# warps_v30.net
KiCad netlist of a schematic drawn in EAGLE
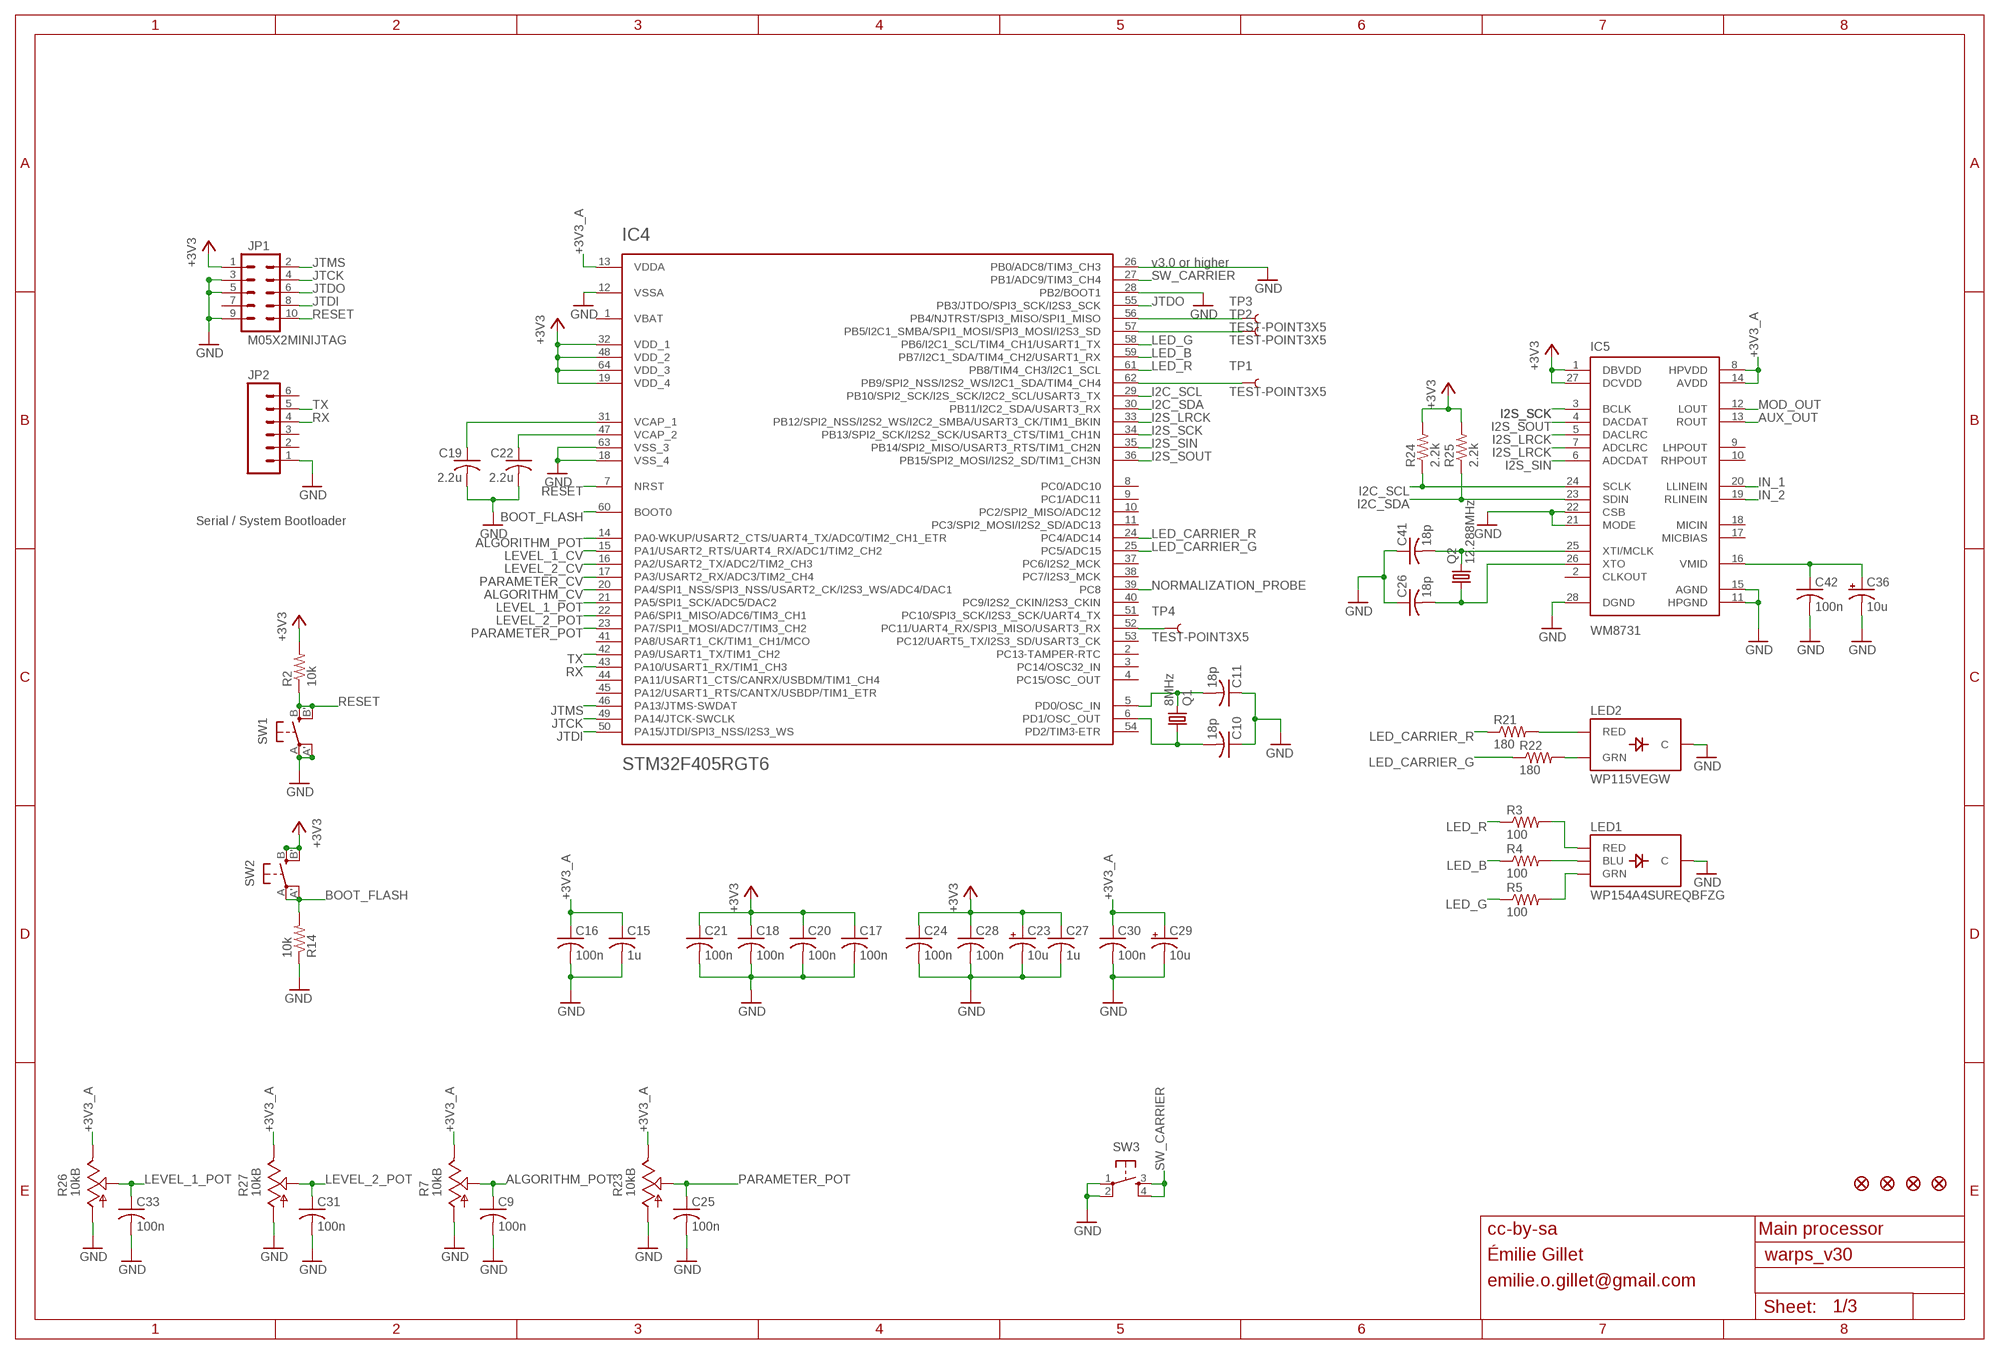
[diagram p0: schematic, sheet 1]
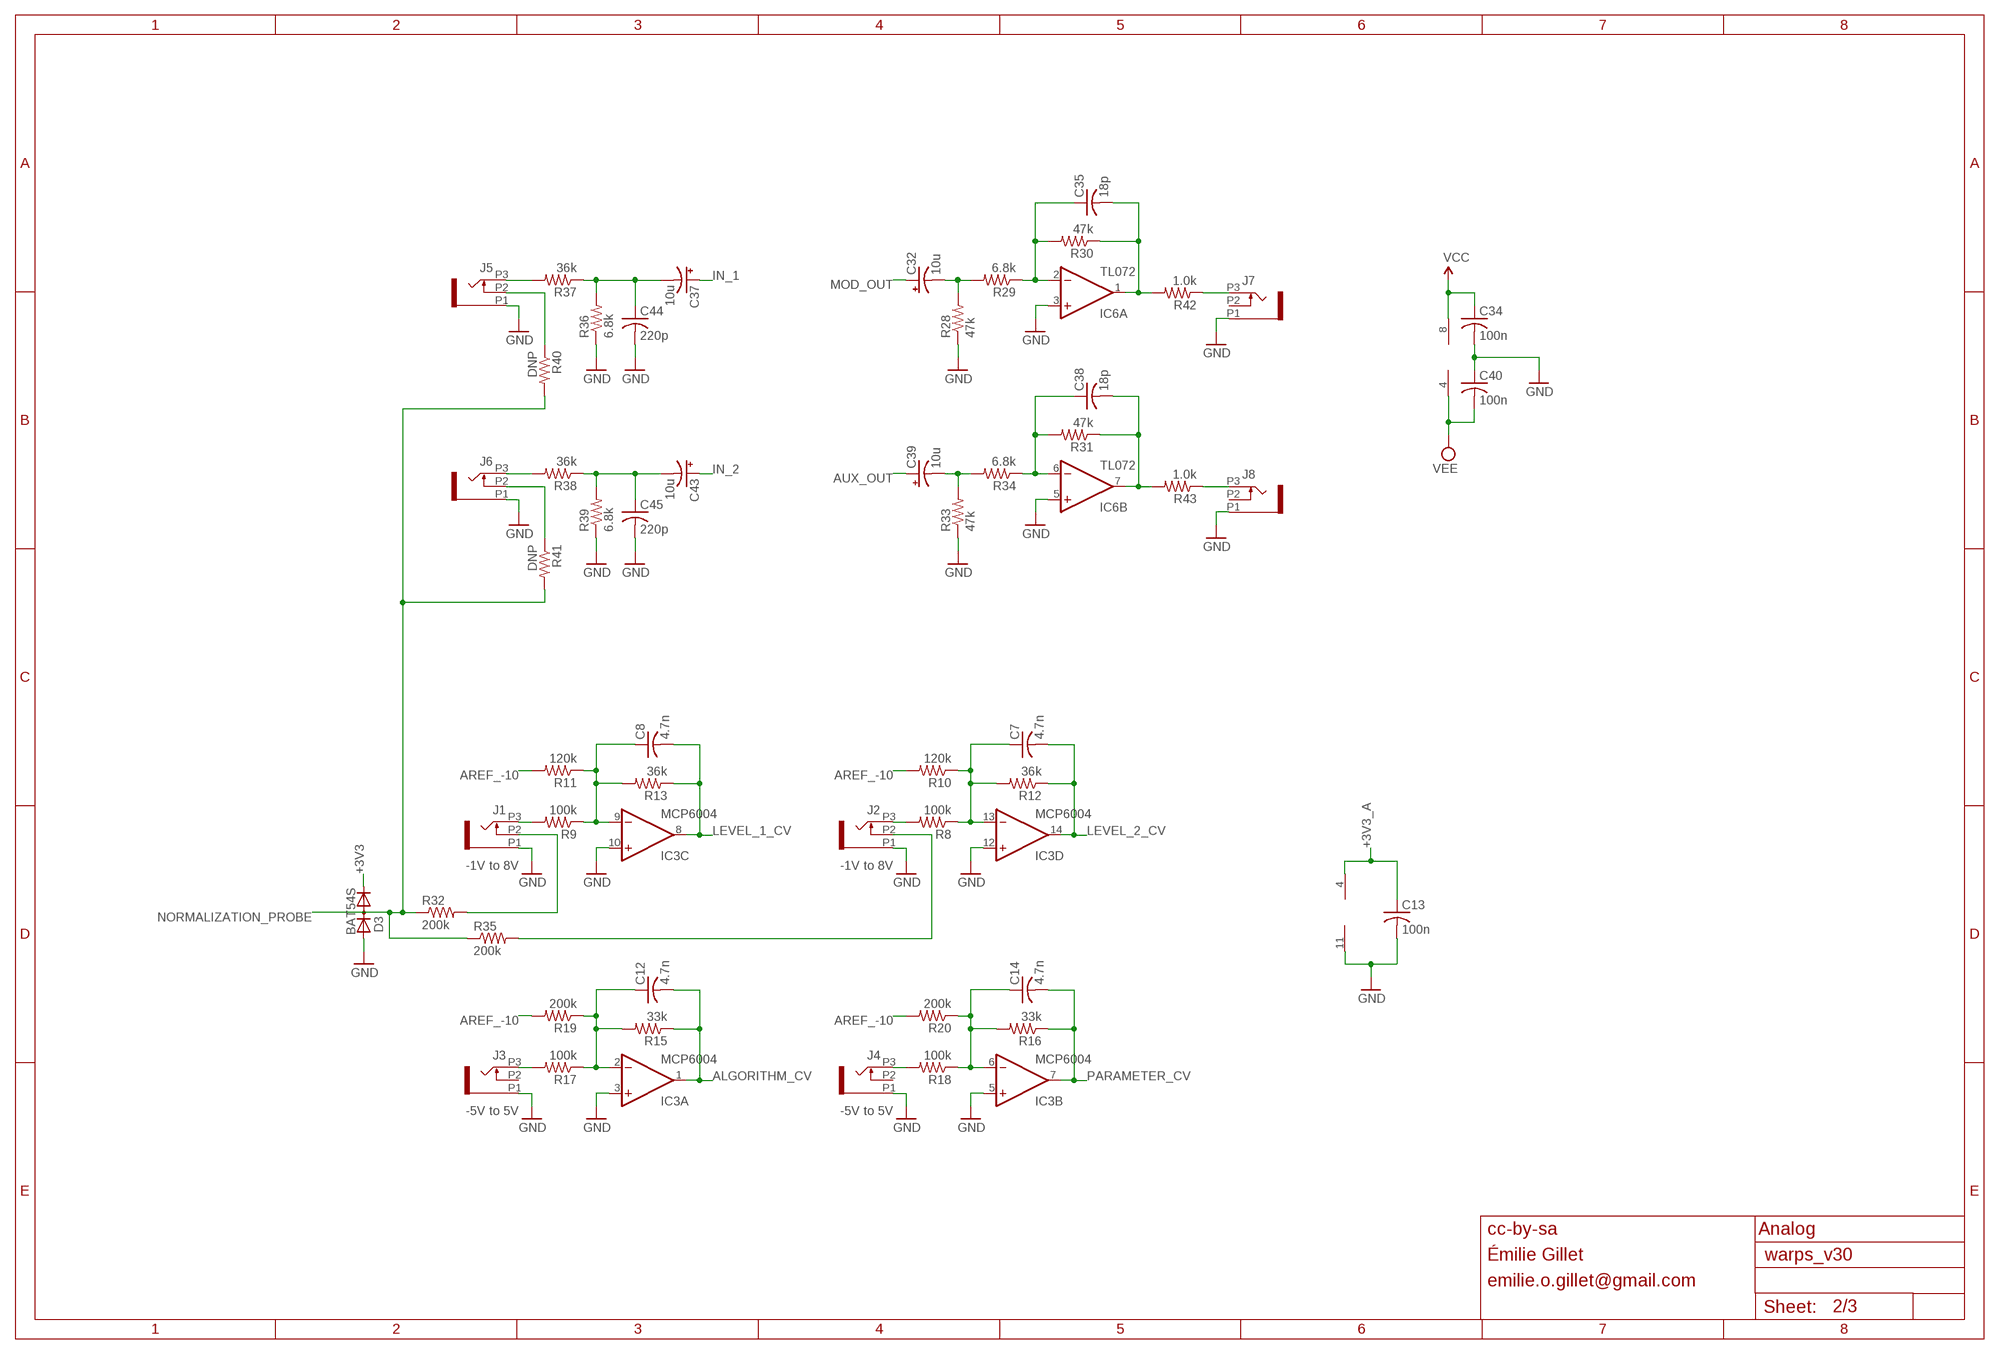
[diagram p1: schematic, sheet 2]
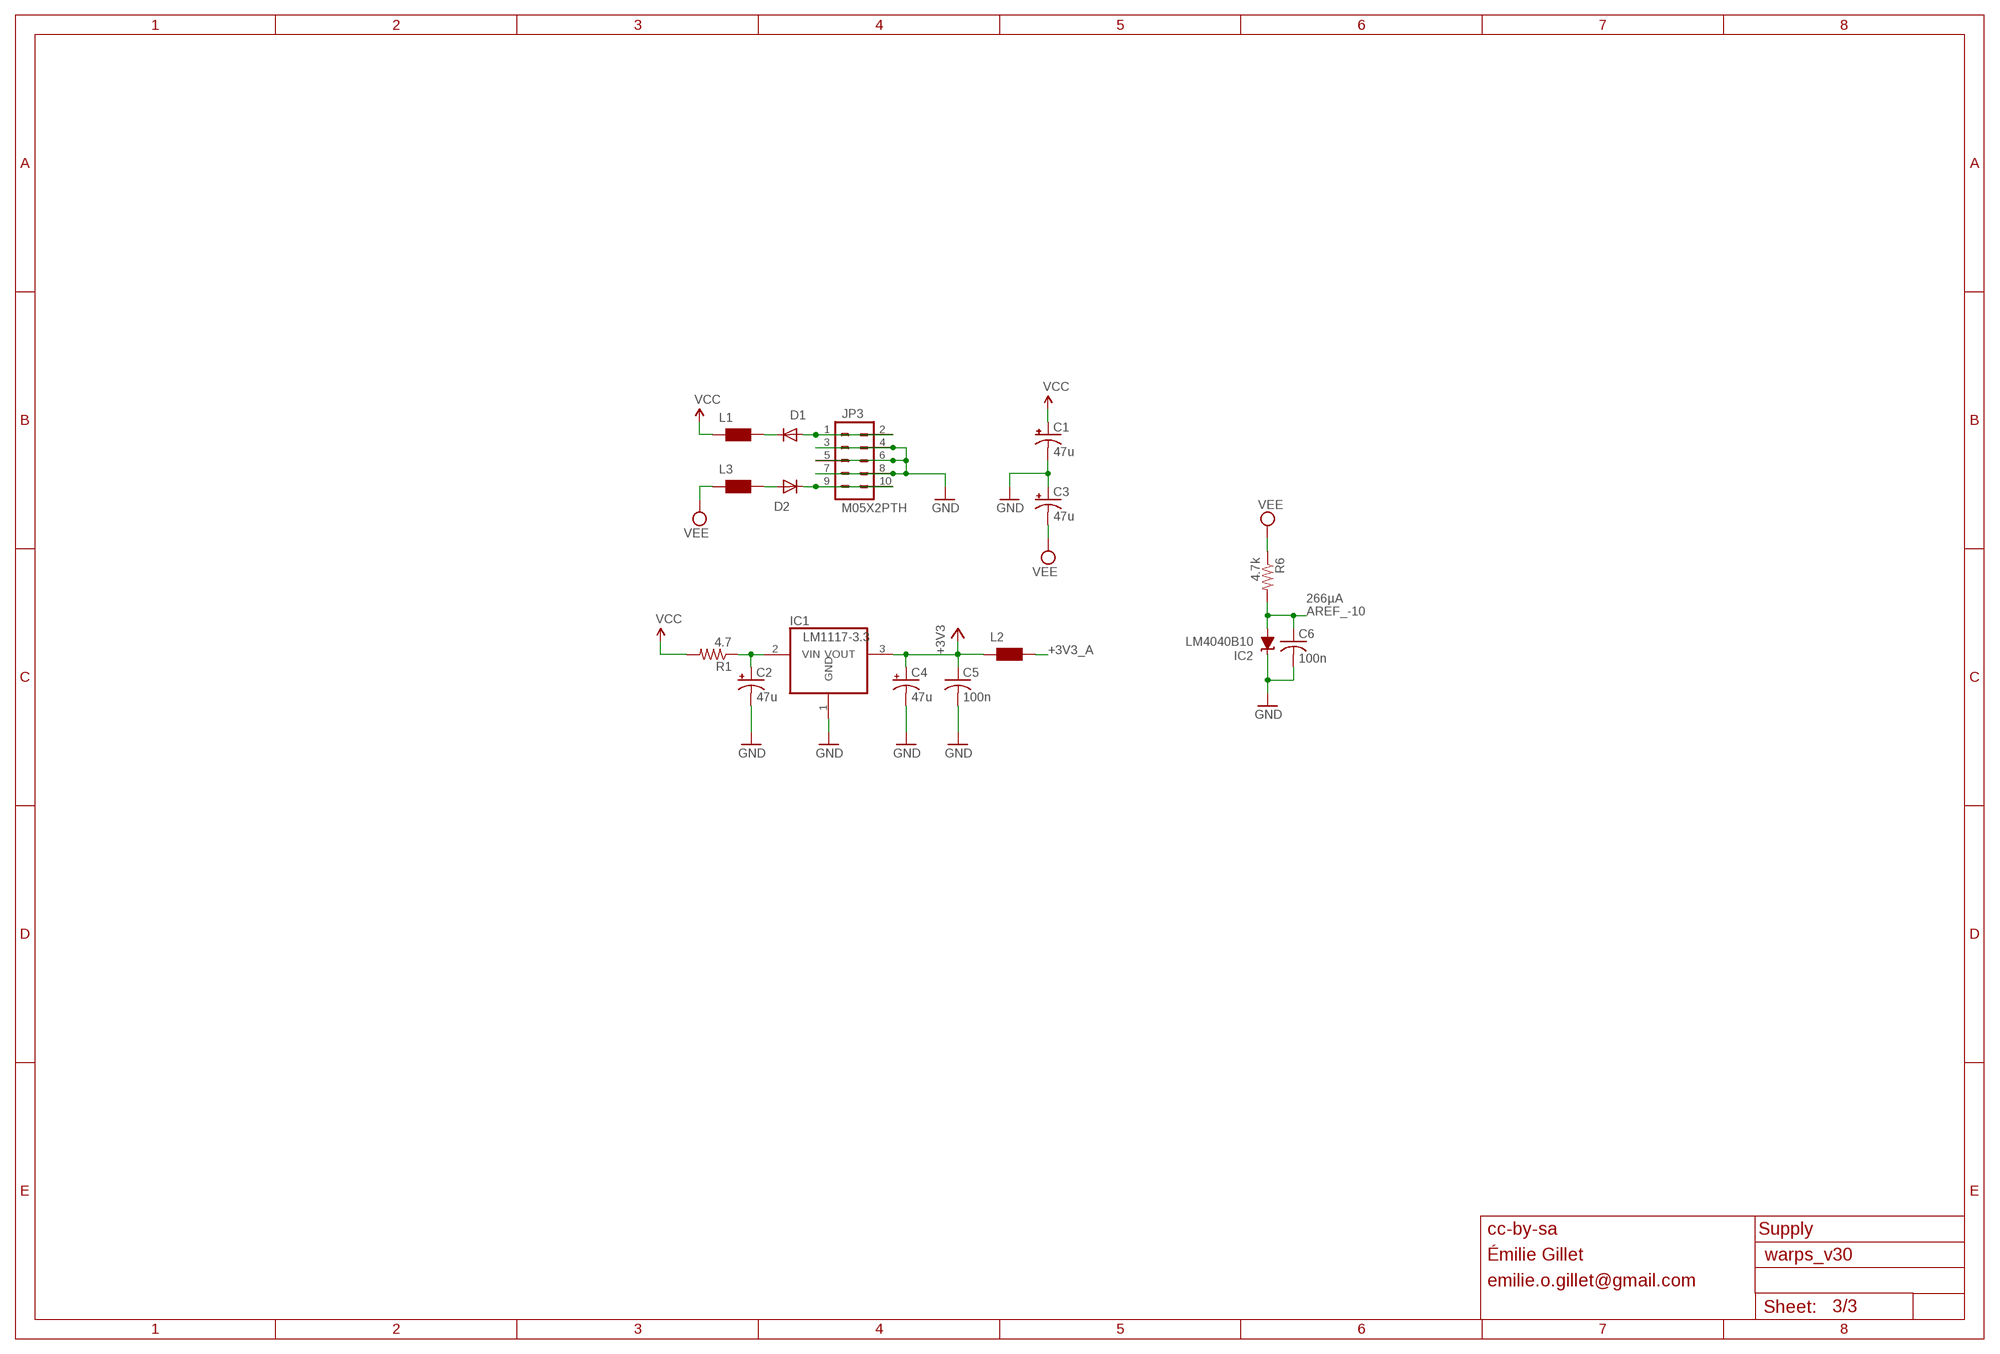
[diagram p2: schematic, sheet 3]

(export (version "E")
  (design (tool "Eeschema 10.0.6"))
  (components
    (comp (ref "C1")
      (value "47u")
      (footprint "eagle-import:PANASONIC_D")
      (libsource (lib "eagle-import") (part "CPOL-USD"))
    )
    (comp (ref "C2")
      (value "47u")
      (footprint "eagle-import:PANASONIC_D")
      (libsource (lib "eagle-import") (part "CPOL-USD"))
    )
    (comp (ref "C3")
      (value "47u")
      (footprint "eagle-import:PANASONIC_D")
      (libsource (lib "eagle-import") (part "CPOL-USD"))
    )
    (comp (ref "C4")
      (value "47u")
      (footprint "eagle-import:PANASONIC_D")
      (libsource (lib "eagle-import") (part "CPOL-USD"))
    )
    (comp (ref "C5")
      (value "100n")
      (footprint "eagle-import:C0603")
      (libsource (lib "eagle-import") (part "C-USC0603"))
    )
    (comp (ref "C6")
      (value "100n")
      (footprint "eagle-import:C0603")
      (libsource (lib "eagle-import") (part "C-USC0603"))
    )
    (comp (ref "D1")
      (value "1N5819HW")
      (footprint "eagle-import:SOD123")
      (libsource (lib "eagle-import") (part "DIODE-SOD123"))
    )
    (comp (ref "D2")
      (value "1N5819HW")
      (footprint "eagle-import:SOD123")
      (libsource (lib "eagle-import") (part "DIODE-SOD123"))
    )
    (comp (ref "IC1")
      (value "LM1117-3.3")
      (footprint "eagle-import:TO252")
      (libsource (lib "eagle-import") (part "REG1117T"))
    )
    (comp (ref "IC2")
      (value "LM4040B10")
      (footprint "eagle-import:DBZ_R-PDSO-G3")
      (libsource (lib "eagle-import") (part "LM4041DBZB12"))
    )
    (comp (ref "JP3")
      (value "M05X2PTH")
      (footprint "eagle-import:AVR_ICSP")
      (libsource (lib "eagle-import") (part "M05X2PTH"))
    )
    (comp (ref "L1")
      (value "WE-CBF_0603")
      (footprint "eagle-import:0603")
      (libsource (lib "eagle-import") (part "WE-CBF_0603"))
    )
    (comp (ref "L2")
      (value "WE-CBF_0603")
      (footprint "eagle-import:0603")
      (libsource (lib "eagle-import") (part "WE-CBF_0603"))
    )
    (comp (ref "L3")
      (value "WE-CBF_0603")
      (footprint "eagle-import:0603")
      (libsource (lib "eagle-import") (part "WE-CBF_0603"))
    )
    (comp (ref "R1")
      (value "4.7")
      (footprint "eagle-import:R1206")
      (libsource (lib "eagle-import") (part "R-US_R1206"))
    )
    (comp (ref "R6")
      (value "4.7k")
      (footprint "eagle-import:R0603")
      (libsource (lib "eagle-import") (part "R-US_R0603"))
    )
    (comp (ref "C7")
      (value "4.7n")
      (footprint "eagle-import:C0603")
      (libsource (lib "eagle-import") (part "C-USC0603"))
    )
    (comp (ref "C8")
      (value "4.7n")
      (footprint "eagle-import:C0603")
      (libsource (lib "eagle-import") (part "C-USC0603"))
    )
    (comp (ref "C12")
      (value "4.7n")
      (footprint "eagle-import:C0603")
      (libsource (lib "eagle-import") (part "C-USC0603"))
    )
    (comp (ref "C13")
      (value "100n")
      (footprint "eagle-import:C0603")
      (libsource (lib "eagle-import") (part "C-USC0603"))
    )
    (comp (ref "C14")
      (value "4.7n")
      (footprint "eagle-import:C0603")
      (libsource (lib "eagle-import") (part "C-USC0603"))
    )
    (comp (ref "C32")
      (value "10u")
      (footprint "eagle-import:PANASONIC_A")
      (libsource (lib "eagle-import") (part "CPOL-USA"))
    )
    (comp (ref "C34")
      (value "100n")
      (footprint "eagle-import:C0603")
      (libsource (lib "eagle-import") (part "C-USC0603"))
    )
    (comp (ref "C35")
      (value "18p")
      (footprint "eagle-import:C0603")
      (libsource (lib "eagle-import") (part "C-USC0603"))
    )
    (comp (ref "C37")
      (value "10u")
      (footprint "eagle-import:PANASONIC_A")
      (libsource (lib "eagle-import") (part "CPOL-USA"))
    )
    (comp (ref "C38")
      (value "18p")
      (footprint "eagle-import:C0603")
      (libsource (lib "eagle-import") (part "C-USC0603"))
    )
    (comp (ref "C39")
      (value "10u")
      (footprint "eagle-import:PANASONIC_A")
      (libsource (lib "eagle-import") (part "CPOL-USA"))
    )
    (comp (ref "C40")
      (value "100n")
      (footprint "eagle-import:C0603")
      (libsource (lib "eagle-import") (part "C-USC0603"))
    )
    (comp (ref "C43")
      (value "10u")
      (footprint "eagle-import:PANASONIC_A")
      (libsource (lib "eagle-import") (part "CPOL-USA"))
    )
    (comp (ref "C44")
      (value "220p")
      (footprint "eagle-import:C0603")
      (libsource (lib "eagle-import") (part "C-USC0603"))
    )
    (comp (ref "C45")
      (value "220p")
      (footprint "eagle-import:C0603")
      (libsource (lib "eagle-import") (part "C-USC0603"))
    )
    (comp (ref "D3")
      (value "BAT54S")
      (footprint "eagle-import:SOT23")
      (libsource (lib "eagle-import") (part "DIODE_2CACA-SOT23"))
    )
    (comp (ref "IC3")
      (value "MCP6004")
      (footprint "eagle-import:SO14")
      (libsource (lib "eagle-import") (part "TL074D"))
    )
    (comp (ref "IC6")
      (value "TL072")
      (footprint "eagle-import:SO08")
      (libsource (lib "eagle-import") (part "TL072D"))
    )
    (comp (ref "J1")
      (value "PJ301_THONKICONN6")
      (footprint "eagle-import:WQP_PJ_301M6")
      (libsource (lib "eagle-import") (part "PJ301_THONKICONN6"))
    )
    (comp (ref "J2")
      (value "PJ301_THONKICONN6")
      (footprint "eagle-import:WQP_PJ_301M6")
      (libsource (lib "eagle-import") (part "PJ301_THONKICONN6"))
    )
    (comp (ref "J3")
      (value "PJ301_THONKICONN6")
      (footprint "eagle-import:WQP_PJ_301M6")
      (libsource (lib "eagle-import") (part "PJ301_THONKICONN6"))
    )
    (comp (ref "J4")
      (value "PJ301_THONKICONN6")
      (footprint "eagle-import:WQP_PJ_301M6")
      (libsource (lib "eagle-import") (part "PJ301_THONKICONN6"))
    )
    (comp (ref "J5")
      (value "PJ301_THONKICONN6")
      (footprint "eagle-import:WQP_PJ_301M6")
      (libsource (lib "eagle-import") (part "PJ301_THONKICONN6"))
    )
    (comp (ref "J6")
      (value "PJ301_THONKICONN6")
      (footprint "eagle-import:WQP_PJ_301M6")
      (libsource (lib "eagle-import") (part "PJ301_THONKICONN6"))
    )
    (comp (ref "J7")
      (value "PJ301_THONKICONN6")
      (footprint "eagle-import:WQP_PJ_301M6")
      (libsource (lib "eagle-import") (part "PJ301_THONKICONN6"))
    )
    (comp (ref "J8")
      (value "PJ301_THONKICONN6")
      (footprint "eagle-import:WQP_PJ_301M6")
      (libsource (lib "eagle-import") (part "PJ301_THONKICONN6"))
    )
    (comp (ref "R8")
      (value "100k")
      (footprint "eagle-import:R0603")
      (libsource (lib "eagle-import") (part "R-US_R0603"))
    )
    (comp (ref "R9")
      (value "100k")
      (footprint "eagle-import:R0603")
      (libsource (lib "eagle-import") (part "R-US_R0603"))
    )
    (comp (ref "R10")
      (value "120k")
      (footprint "eagle-import:R0603")
      (libsource (lib "eagle-import") (part "R-US_R0603"))
    )
    (comp (ref "R11")
      (value "120k")
      (footprint "eagle-import:R0603")
      (libsource (lib "eagle-import") (part "R-US_R0603"))
    )
    (comp (ref "R12")
      (value "36k")
      (footprint "eagle-import:R0603")
      (libsource (lib "eagle-import") (part "R-US_R0603"))
    )
    (comp (ref "R13")
      (value "36k")
      (footprint "eagle-import:R0603")
      (libsource (lib "eagle-import") (part "R-US_R0603"))
    )
    (comp (ref "R15")
      (value "33k")
      (footprint "eagle-import:R0603")
      (libsource (lib "eagle-import") (part "R-US_R0603"))
    )
    (comp (ref "R16")
      (value "33k")
      (footprint "eagle-import:R0603")
      (libsource (lib "eagle-import") (part "R-US_R0603"))
    )
    (comp (ref "R17")
      (value "100k")
      (footprint "eagle-import:R0603")
      (libsource (lib "eagle-import") (part "R-US_R0603"))
    )
    (comp (ref "R18")
      (value "100k")
      (footprint "eagle-import:R0603")
      (libsource (lib "eagle-import") (part "R-US_R0603"))
    )
    (comp (ref "R19")
      (value "200k")
      (footprint "eagle-import:R0603")
      (libsource (lib "eagle-import") (part "R-US_R0603"))
    )
    (comp (ref "R20")
      (value "200k")
      (footprint "eagle-import:R0603")
      (libsource (lib "eagle-import") (part "R-US_R0603"))
    )
    (comp (ref "R28")
      (value "47k")
      (footprint "eagle-import:R0603")
      (libsource (lib "eagle-import") (part "R-US_R0603"))
    )
    (comp (ref "R29")
      (value "6.8k")
      (footprint "eagle-import:R0603")
      (libsource (lib "eagle-import") (part "R-US_R0603"))
    )
    (comp (ref "R30")
      (value "47k")
      (footprint "eagle-import:R0603")
      (libsource (lib "eagle-import") (part "R-US_R0603"))
    )
    (comp (ref "R31")
      (value "47k")
      (footprint "eagle-import:R0603")
      (libsource (lib "eagle-import") (part "R-US_R0603"))
    )
    (comp (ref "R32")
      (value "200k")
      (footprint "eagle-import:R0603")
      (libsource (lib "eagle-import") (part "R-US_R0603"))
    )
    (comp (ref "R33")
      (value "47k")
      (footprint "eagle-import:R0603")
      (libsource (lib "eagle-import") (part "R-US_R0603"))
    )
    (comp (ref "R34")
      (value "6.8k")
      (footprint "eagle-import:R0603")
      (libsource (lib "eagle-import") (part "R-US_R0603"))
    )
    (comp (ref "R35")
      (value "200k")
      (footprint "eagle-import:R0603")
      (libsource (lib "eagle-import") (part "R-US_R0603"))
    )
    (comp (ref "R36")
      (value "6.8k")
      (footprint "eagle-import:R0603")
      (libsource (lib "eagle-import") (part "R-US_R0603"))
    )
    (comp (ref "R37")
      (value "36k")
      (footprint "eagle-import:R0603")
      (libsource (lib "eagle-import") (part "R-US_R0603"))
    )
    (comp (ref "R38")
      (value "36k")
      (footprint "eagle-import:R0603")
      (libsource (lib "eagle-import") (part "R-US_R0603"))
    )
    (comp (ref "R39")
      (value "6.8k")
      (footprint "eagle-import:R0603")
      (libsource (lib "eagle-import") (part "R-US_R0603"))
    )
    (comp (ref "R40")
      (value "DNP")
      (footprint "eagle-import:R0603")
      (libsource (lib "eagle-import") (part "R-US_R0603"))
    )
    (comp (ref "R41")
      (value "DNP")
      (footprint "eagle-import:R0603")
      (libsource (lib "eagle-import") (part "R-US_R0603"))
    )
    (comp (ref "R42")
      (value "1.0k")
      (footprint "eagle-import:R0603")
      (libsource (lib "eagle-import") (part "R-US_R0603"))
    )
    (comp (ref "R43")
      (value "1.0k")
      (footprint "eagle-import:R0603")
      (libsource (lib "eagle-import") (part "R-US_R0603"))
    )
    (comp (ref "C9")
      (value "100n")
      (footprint "eagle-import:C0603")
      (libsource (lib "eagle-import") (part "C-USC0603"))
    )
    (comp (ref "C10")
      (value "18p")
      (footprint "eagle-import:C0603")
      (libsource (lib "eagle-import") (part "C-USC0603"))
    )
    (comp (ref "C11")
      (value "18p")
      (footprint "eagle-import:C0603")
      (libsource (lib "eagle-import") (part "C-USC0603"))
    )
    (comp (ref "C15")
      (value "1u")
      (footprint "eagle-import:C0603")
      (libsource (lib "eagle-import") (part "C-USC0603"))
    )
    (comp (ref "C16")
      (value "100n")
      (footprint "eagle-import:C0603")
      (libsource (lib "eagle-import") (part "C-USC0603"))
    )
    (comp (ref "C17")
      (value "100n")
      (footprint "eagle-import:C0603")
      (libsource (lib "eagle-import") (part "C-USC0603"))
    )
    (comp (ref "C18")
      (value "100n")
      (footprint "eagle-import:C0603")
      (libsource (lib "eagle-import") (part "C-USC0603"))
    )
    (comp (ref "C19")
      (value "2.2u")
      (footprint "eagle-import:C0805")
      (libsource (lib "eagle-import") (part "C-USC0805"))
    )
    (comp (ref "C20")
      (value "100n")
      (footprint "eagle-import:C0603")
      (libsource (lib "eagle-import") (part "C-USC0603"))
    )
    (comp (ref "C21")
      (value "100n")
      (footprint "eagle-import:C0603")
      (libsource (lib "eagle-import") (part "C-USC0603"))
    )
    (comp (ref "C22")
      (value "2.2u")
      (footprint "eagle-import:C0805")
      (libsource (lib "eagle-import") (part "C-USC0805"))
    )
    (comp (ref "C23")
      (value "10u")
      (footprint "eagle-import:PANASONIC_A")
      (libsource (lib "eagle-import") (part "CPOL-USA"))
    )
    (comp (ref "C24")
      (value "100n")
      (footprint "eagle-import:C0603")
      (libsource (lib "eagle-import") (part "C-USC0603"))
    )
    (comp (ref "C25")
      (value "100n")
      (footprint "eagle-import:C0603")
      (libsource (lib "eagle-import") (part "C-USC0603"))
    )
    (comp (ref "C26")
      (value "18p")
      (footprint "eagle-import:C0603")
      (libsource (lib "eagle-import") (part "C-USC0603"))
    )
    (comp (ref "C27")
      (value "1u")
      (footprint "eagle-import:C0603")
      (libsource (lib "eagle-import") (part "C-USC0603"))
    )
    (comp (ref "C28")
      (value "100n")
      (footprint "eagle-import:C0603")
      (libsource (lib "eagle-import") (part "C-USC0603"))
    )
    (comp (ref "C29")
      (value "10u")
      (footprint "eagle-import:PANASONIC_A")
      (libsource (lib "eagle-import") (part "CPOL-USA"))
    )
    (comp (ref "C30")
      (value "100n")
      (footprint "eagle-import:C0603")
      (libsource (lib "eagle-import") (part "C-USC0603"))
    )
    (comp (ref "C31")
      (value "100n")
      (footprint "eagle-import:C0603")
      (libsource (lib "eagle-import") (part "C-USC0603"))
    )
    (comp (ref "C33")
      (value "100n")
      (footprint "eagle-import:C0603")
      (libsource (lib "eagle-import") (part "C-USC0603"))
    )
    (comp (ref "C36")
      (value "10u")
      (footprint "eagle-import:PANASONIC_A")
      (libsource (lib "eagle-import") (part "CPOL-USA"))
    )
    (comp (ref "C41")
      (value "18p")
      (footprint "eagle-import:C0603")
      (libsource (lib "eagle-import") (part "C-USC0603"))
    )
    (comp (ref "C42")
      (value "100n")
      (footprint "eagle-import:C0603")
      (libsource (lib "eagle-import") (part "C-USC0603"))
    )
    (comp (ref "F1")
      (value "FIDUCIAL1X2")
      (footprint "eagle-import:FIDUCIAL-1X2")
      (libsource (lib "eagle-import") (part "FIDUCIAL1X2"))
    )
    (comp (ref "F2")
      (value "FIDUCIAL1X2")
      (footprint "eagle-import:FIDUCIAL-1X2")
      (libsource (lib "eagle-import") (part "FIDUCIAL1X2"))
    )
    (comp (ref "F3")
      (value "FIDUCIAL1X2")
      (footprint "eagle-import:FIDUCIAL-1X2")
      (libsource (lib "eagle-import") (part "FIDUCIAL1X2"))
    )
    (comp (ref "F4")
      (value "FIDUCIAL1X2")
      (footprint "eagle-import:FIDUCIAL-1X2")
      (libsource (lib "eagle-import") (part "FIDUCIAL1X2"))
    )
    (comp (ref "IC4")
      (value "STM32F405RGT6")
      (footprint "eagle-import:TQFP-10X10-64")
      (libsource (lib "eagle-import") (part "STM32F20X"))
    )
    (comp (ref "IC5")
      (value "WM8731")
      (footprint "eagle-import:SSOP28")
      (libsource (lib "eagle-import") (part "WM8731"))
    )
    (comp (ref "JP1")
      (value "M05X2MINIJTAG")
      (footprint "eagle-import:2X5-1.27")
      (libsource (lib "eagle-import") (part "M05X2MINIJTAG"))
    )
    (comp (ref "JP2")
      (value "M06SIP")
      (footprint "eagle-import:1X06")
      (libsource (lib "eagle-import") (part "M06SIP"))
    )
    (comp (ref "LED1")
      (value "WP154A4SUREQBFZG")
      (footprint "eagle-import:LED-TRICOLOR-THROUGHHOLE")
      (libsource (lib "eagle-import") (part "LED-TRICOLOR-THROUGHHOLE"))
    )
    (comp (ref "LED2")
      (value "WP115VEGW")
      (footprint "eagle-import:LED-BICOLOR-THROUGHHOLE")
      (libsource (lib "eagle-import") (part "LED-BICOLOR-THROUGHHOLE"))
    )
    (comp (ref "Q1")
      (value "8MHz")
      (footprint "eagle-import:HC49UP")
      (libsource (lib "eagle-import") (part "CRYSTALHC49UP"))
    )
    (comp (ref "Q2")
      (value "12.288MHz")
      (footprint "eagle-import:HC49UP")
      (libsource (lib "eagle-import") (part "CRYSTALHC49UP"))
    )
    (comp (ref "R2")
      (value "10k")
      (footprint "eagle-import:R0603")
      (libsource (lib "eagle-import") (part "R-US_R0603"))
    )
    (comp (ref "R3")
      (value "100")
      (footprint "eagle-import:R0603")
      (libsource (lib "eagle-import") (part "R-US_R0603"))
    )
    (comp (ref "R4")
      (value "100")
      (footprint "eagle-import:R0603")
      (libsource (lib "eagle-import") (part "R-US_R0603"))
    )
    (comp (ref "R5")
      (value "100")
      (footprint "eagle-import:R0603")
      (libsource (lib "eagle-import") (part "R-US_R0603"))
    )
    (comp (ref "R7")
      (value "10kB")
      (footprint "eagle-import:ALPS_POT_VERTICAL_PS")
      (libsource (lib "eagle-import") (part "POT_USVERTICAL_PS"))
    )
    (comp (ref "R14")
      (value "10k")
      (footprint "eagle-import:R0603")
      (libsource (lib "eagle-import") (part "R-US_R0603"))
    )
    (comp (ref "R21")
      (value "180")
      (footprint "eagle-import:R0603")
      (libsource (lib "eagle-import") (part "R-US_R0603"))
    )
    (comp (ref "R22")
      (value "180")
      (footprint "eagle-import:R0603")
      (libsource (lib "eagle-import") (part "R-US_R0603"))
    )
    (comp (ref "R23")
      (value "10kB")
      (footprint "eagle-import:ALPS_POT_VERTICAL_PS")
      (libsource (lib "eagle-import") (part "POT_USVERTICAL_PS"))
    )
    (comp (ref "R24")
      (value "2.2k")
      (footprint "eagle-import:R0603")
      (libsource (lib "eagle-import") (part "R-US_R0603"))
    )
    (comp (ref "R25")
      (value "2.2k")
      (footprint "eagle-import:R0603")
      (libsource (lib "eagle-import") (part "R-US_R0603"))
    )
    (comp (ref "R26")
      (value "10kB")
      (footprint "eagle-import:ALPS_POT_VERTICAL")
      (libsource (lib "eagle-import") (part "POT_USVERTICAL"))
    )
    (comp (ref "R27")
      (value "10kB")
      (footprint "eagle-import:ALPS_POT_VERTICAL")
      (libsource (lib "eagle-import") (part "POT_USVERTICAL"))
    )
    (comp (ref "SW1")
      (value "EVQQ2")
      (footprint "eagle-import:EVQ-Q2")
      (libsource (lib "eagle-import") (part "EVQQ2"))
    )
    (comp (ref "SW2")
      (value "EVQQ2")
      (footprint "eagle-import:EVQ-Q2")
      (libsource (lib "eagle-import") (part "EVQQ2"))
    )
    (comp (ref "SW3")
      (value "TAC_SWITCHPTH")
      (footprint "eagle-import:TACTILE-PTH")
      (libsource (lib "eagle-import") (part "TAC_SWITCHPTH"))
    )
    (comp (ref "TP1")
      (value "TEST-POINT3X5")
      (footprint "eagle-import:PAD.03X.05")
      (libsource (lib "eagle-import") (part "TEST-POINT3X5"))
    )
    (comp (ref "TP2")
      (value "TEST-POINT3X5")
      (footprint "eagle-import:PAD.03X.05")
      (libsource (lib "eagle-import") (part "TEST-POINT3X5"))
    )
    (comp (ref "TP3")
      (value "TEST-POINT3X5")
      (footprint "eagle-import:PAD.03X.05")
      (libsource (lib "eagle-import") (part "TEST-POINT3X5"))
    )
    (comp (ref "TP4")
      (value "TEST-POINT3X5")
      (footprint "eagle-import:PAD.03X.05")
      (libsource (lib "eagle-import") (part "TEST-POINT3X5"))
    )
  )
  (nets
    (net (code "1") (name "+3V3") (class "Default")
      (node (ref "C17") (pin "1") (pinfunction "1_1") (pintype "passive"))
      (node (ref "C18") (pin "1") (pinfunction "1_1") (pintype "passive"))
      (node (ref "C20") (pin "1") (pinfunction "1_1") (pintype "passive"))
      (node (ref "C21") (pin "1") (pinfunction "1_1") (pintype "passive"))
      (node (ref "C23") (pin "+") (pinfunction "+_+") (pintype "passive"))
      (node (ref "C24") (pin "1") (pinfunction "1_1") (pintype "passive"))
      (node (ref "C27") (pin "1") (pinfunction "1_1") (pintype "passive"))
      (node (ref "C28") (pin "1") (pinfunction "1_1") (pintype "passive"))
      (node (ref "C4") (pin "+") (pinfunction "+_+") (pintype "passive"))
      (node (ref "C5") (pin "1") (pinfunction "1_1") (pintype "passive"))
      (node (ref "D3") (pin "2") (pinfunction "C_2") (pintype "passive"))
      (node (ref "IC1") (pin "3") (pinfunction "VOUT_3") (pintype "output"))
      (node (ref "IC4") (pin "19") (pinfunction "VDD_4_19") (pintype "power_in"))
      (node (ref "IC4") (pin "32") (pinfunction "VDD_1_32") (pintype "power_in"))
      (node (ref "IC4") (pin "48") (pinfunction "VDD_2_48") (pintype "power_in"))
      (node (ref "IC4") (pin "64") (pinfunction "VDD_3_64") (pintype "power_in"))
      (node (ref "IC5") (pin "1") (pinfunction "DBVDD_1") (pintype "bidirectional"))
      (node (ref "IC5") (pin "27") (pinfunction "DCVDD_27") (pintype "bidirectional"))
      (node (ref "JP1") (pin "1") (pinfunction "1_1") (pintype "passive"))
      (node (ref "L2") (pin "1") (pinfunction "1_1") (pintype "passive"))
      (node (ref "R2") (pin "2") (pinfunction "2_2") (pintype "passive"))
      (node (ref "R24") (pin "2") (pinfunction "2_2") (pintype "passive"))
      (node (ref "R25") (pin "2") (pinfunction "2_2") (pintype "passive"))
      (node (ref "SW2") (pin "B") (pinfunction "S_B") (pintype "passive"))
      (node (ref "SW2") (pin "B'") (pinfunction "S1_B'") (pintype "passive"))
    )
    (net (code "2") (name "+3V3_A") (class "Default")
      (node (ref "C13") (pin "1") (pinfunction "1_1") (pintype "passive"))
      (node (ref "C15") (pin "1") (pinfunction "1_1") (pintype "passive"))
      (node (ref "C16") (pin "1") (pinfunction "1_1") (pintype "passive"))
      (node (ref "C29") (pin "+") (pinfunction "+_+") (pintype "passive"))
      (node (ref "C30") (pin "1") (pinfunction "1_1") (pintype "passive"))
      (node (ref "IC3") (pin "4") (pinfunction "V+_4") (pintype "power_in"))
      (node (ref "IC4") (pin "13") (pinfunction "VDDA_13") (pintype "power_in"))
      (node (ref "IC5") (pin "14") (pinfunction "AVDD_14") (pintype "bidirectional"))
      (node (ref "IC5") (pin "8") (pinfunction "HPVDD_8") (pintype "bidirectional"))
      (node (ref "L2") (pin "2") (pinfunction "2_2") (pintype "passive"))
      (node (ref "R23") (pin "P$1") (pinfunction "E_P$1") (pintype "passive"))
      (node (ref "R26") (pin "P$1") (pinfunction "E_P$1") (pintype "passive"))
      (node (ref "R27") (pin "P$1") (pinfunction "E_P$1") (pintype "passive"))
      (node (ref "R7") (pin "P$1") (pinfunction "E_P$1") (pintype "passive"))
    )
    (net (code "3") (name "ALGORITHM_CV") (class "Default")
      (node (ref "C12") (pin "2") (pinfunction "2_2") (pintype "passive"))
      (node (ref "IC3") (pin "1") (pinfunction "OUT_1") (pintype "output"))
      (node (ref "IC4") (pin "20") (pinfunction "PA4/SPI1_NSS/SPI3_NSS/USART2_CK/I2S3_WS/ADC4/DAC1_20") (pintype "bidirectional"))
      (node (ref "R15") (pin "1") (pinfunction "1_1") (pintype "passive"))
    )
    (net (code "4") (name "ALGORITHM_POT") (class "Default")
      (node (ref "C9") (pin "1") (pinfunction "1_1") (pintype "passive"))
      (node (ref "IC4") (pin "14") (pinfunction "PA0-WKUP/USART2_CTS/UART4_TX/ADC0/TIM2_CH1_ETR_14") (pintype "bidirectional"))
      (node (ref "R7") (pin "P$2") (pinfunction "S_P$2") (pintype "passive"))
    )
    (net (code "5") (name "AREF_-10") (class "Default")
      (node (ref "C6") (pin "1") (pinfunction "1_1") (pintype "passive"))
      (node (ref "IC2") (pin "2") (pinfunction "A_2") (pintype "passive"))
      (node (ref "R10") (pin "2") (pinfunction "2_2") (pintype "passive"))
      (node (ref "R11") (pin "2") (pinfunction "2_2") (pintype "passive"))
      (node (ref "R19") (pin "2") (pinfunction "2_2") (pintype "passive"))
      (node (ref "R20") (pin "2") (pinfunction "2_2") (pintype "passive"))
      (node (ref "R6") (pin "2") (pinfunction "2_2") (pintype "passive"))
    )
    (net (code "6") (name "AUX_OUT") (class "Default")
      (node (ref "C39") (pin "+") (pinfunction "+_+") (pintype "passive"))
      (node (ref "IC5") (pin "13") (pinfunction "ROUT_13") (pintype "bidirectional"))
    )
    (net (code "7") (name "BOOT_FLASH") (class "Default")
      (node (ref "IC4") (pin "60") (pinfunction "BOOT0_60") (pintype "bidirectional"))
      (node (ref "R14") (pin "2") (pinfunction "2_2") (pintype "passive"))
      (node (ref "SW2") (pin "A") (pinfunction "P_A") (pintype "passive"))
      (node (ref "SW2") (pin "A'") (pinfunction "P1_A'") (pintype "passive"))
    )
    (net (code "8") (name "GND") (class "Default")
      (node (ref "C1") (pin "-") (pinfunction "-_-") (pintype "passive"))
      (node (ref "C10") (pin "1") (pinfunction "1_1") (pintype "passive"))
      (node (ref "C11") (pin "1") (pinfunction "1_1") (pintype "passive"))
      (node (ref "C13") (pin "2") (pinfunction "2_2") (pintype "passive"))
      (node (ref "C15") (pin "2") (pinfunction "2_2") (pintype "passive"))
      (node (ref "C16") (pin "2") (pinfunction "2_2") (pintype "passive"))
      (node (ref "C17") (pin "2") (pinfunction "2_2") (pintype "passive"))
      (node (ref "C18") (pin "2") (pinfunction "2_2") (pintype "passive"))
      (node (ref "C19") (pin "2") (pinfunction "2_2") (pintype "passive"))
      (node (ref "C2") (pin "-") (pinfunction "-_-") (pintype "passive"))
      (node (ref "C20") (pin "2") (pinfunction "2_2") (pintype "passive"))
      (node (ref "C21") (pin "2") (pinfunction "2_2") (pintype "passive"))
      (node (ref "C22") (pin "2") (pinfunction "2_2") (pintype "passive"))
      (node (ref "C23") (pin "-") (pinfunction "-_-") (pintype "passive"))
      (node (ref "C24") (pin "2") (pinfunction "2_2") (pintype "passive"))
      (node (ref "C25") (pin "2") (pinfunction "2_2") (pintype "passive"))
      (node (ref "C26") (pin "1") (pinfunction "1_1") (pintype "passive"))
      (node (ref "C27") (pin "2") (pinfunction "2_2") (pintype "passive"))
      (node (ref "C28") (pin "2") (pinfunction "2_2") (pintype "passive"))
      (node (ref "C29") (pin "-") (pinfunction "-_-") (pintype "passive"))
      (node (ref "C3") (pin "+") (pinfunction "+_+") (pintype "passive"))
      (node (ref "C30") (pin "2") (pinfunction "2_2") (pintype "passive"))
      (node (ref "C31") (pin "2") (pinfunction "2_2") (pintype "passive"))
      (node (ref "C33") (pin "2") (pinfunction "2_2") (pintype "passive"))
      (node (ref "C34") (pin "2") (pinfunction "2_2") (pintype "passive"))
      (node (ref "C36") (pin "-") (pinfunction "-_-") (pintype "passive"))
      (node (ref "C4") (pin "-") (pinfunction "-_-") (pintype "passive"))
      (node (ref "C40") (pin "1") (pinfunction "1_1") (pintype "passive"))
      (node (ref "C41") (pin "1") (pinfunction "1_1") (pintype "passive"))
      (node (ref "C42") (pin "2") (pinfunction "2_2") (pintype "passive"))
      (node (ref "C44") (pin "2") (pinfunction "2_2") (pintype "passive"))
      (node (ref "C45") (pin "2") (pinfunction "2_2") (pintype "passive"))
      (node (ref "C5") (pin "2") (pinfunction "2_2") (pintype "passive"))
      (node (ref "C6") (pin "2") (pinfunction "2_2") (pintype "passive"))
      (node (ref "C9") (pin "2") (pinfunction "2_2") (pintype "passive"))
      (node (ref "D3") (pin "1") (pinfunction "A_1") (pintype "passive"))
      (node (ref "IC1") (pin "1") (pinfunction "GND_1") (pintype "power_in"))
      (node (ref "IC2") (pin "1") (pinfunction "C_1") (pintype "passive"))
      (node (ref "IC3") (pin "10") (pinfunction "+IN_10") (pintype "input"))
      (node (ref "IC3") (pin "11") (pinfunction "V-_11") (pintype "power_in"))
      (node (ref "IC3") (pin "12") (pinfunction "+IN_12") (pintype "input"))
      (node (ref "IC3") (pin "3") (pinfunction "+IN_3") (pintype "input"))
      (node (ref "IC3") (pin "5") (pinfunction "+IN_5") (pintype "input"))
      (node (ref "IC4") (pin "12") (pinfunction "VSSA_12") (pintype "power_in"))
      (node (ref "IC4") (pin "18") (pinfunction "VSS_4_18") (pintype "power_in"))
      (node (ref "IC4") (pin "26") (pinfunction "PB0/ADC8/TIM3_CH3_26") (pintype "bidirectional"))
      (node (ref "IC4") (pin "28") (pinfunction "PB2/BOOT1_28") (pintype "bidirectional"))
      (node (ref "IC4") (pin "63") (pinfunction "VSS_3_63") (pintype "power_in"))
      (node (ref "IC5") (pin "11") (pinfunction "HPGND_11") (pintype "bidirectional"))
      (node (ref "IC5") (pin "15") (pinfunction "AGND_15") (pintype "bidirectional"))
      (node (ref "IC5") (pin "21") (pinfunction "MODE_21") (pintype "bidirectional"))
      (node (ref "IC5") (pin "22") (pinfunction "CSB_22") (pintype "bidirectional"))
      (node (ref "IC5") (pin "28") (pinfunction "DGND_28") (pintype "bidirectional"))
      (node (ref "IC6") (pin "3") (pinfunction "+IN_3") (pintype "input"))
      (node (ref "IC6") (pin "5") (pinfunction "+IN_5") (pintype "input"))
      (node (ref "J1") (pin "P1") (pinfunction "1_P1") (pintype "passive"))
      (node (ref "J2") (pin "P1") (pinfunction "1_P1") (pintype "passive"))
      (node (ref "J3") (pin "P1") (pinfunction "1_P1") (pintype "passive"))
      (node (ref "J4") (pin "P1") (pinfunction "1_P1") (pintype "passive"))
      (node (ref "J5") (pin "P1") (pinfunction "1_P1") (pintype "passive"))
      (node (ref "J6") (pin "P1") (pinfunction "1_P1") (pintype "passive"))
      (node (ref "J7") (pin "P1") (pinfunction "1_P1") (pintype "passive"))
      (node (ref "J8") (pin "P1") (pinfunction "1_P1") (pintype "passive"))
      (node (ref "JP1") (pin "3") (pinfunction "3_3") (pintype "passive"))
      (node (ref "JP1") (pin "5") (pinfunction "5_5") (pintype "passive"))
      (node (ref "JP1") (pin "9") (pinfunction "9_9") (pintype "passive"))
      (node (ref "JP2") (pin "1") (pinfunction "1_1") (pintype "passive"))
      (node (ref "JP3") (pin "3") (pinfunction "3_3") (pintype "passive"))
      (node (ref "JP3") (pin "4") (pinfunction "4_4") (pintype "passive"))
      (node (ref "JP3") (pin "5") (pinfunction "5_5") (pintype "passive"))
      (node (ref "JP3") (pin "6") (pinfunction "6_6") (pintype "passive"))
      (node (ref "JP3") (pin "7") (pinfunction "7_7") (pintype "passive"))
      (node (ref "JP3") (pin "8") (pinfunction "8_8") (pintype "passive"))
      (node (ref "LED1") (pin "GND") (pinfunction "C_GND") (pintype "bidirectional"))
      (node (ref "LED2") (pin "2") (pinfunction "C_2") (pintype "bidirectional"))
      (node (ref "R14") (pin "1") (pinfunction "1_1") (pintype "passive"))
      (node (ref "R23") (pin "P$3") (pinfunction "A_P$3") (pintype "passive"))
      (node (ref "R26") (pin "P$3") (pinfunction "A_P$3") (pintype "passive"))
      (node (ref "R27") (pin "P$3") (pinfunction "A_P$3") (pintype "passive"))
      (node (ref "R28") (pin "1") (pinfunction "1_1") (pintype "passive"))
      (node (ref "R33") (pin "1") (pinfunction "1_1") (pintype "passive"))
      (node (ref "R36") (pin "1") (pinfunction "1_1") (pintype "passive"))
      (node (ref "R39") (pin "1") (pinfunction "1_1") (pintype "passive"))
      (node (ref "R7") (pin "P$3") (pinfunction "A_P$3") (pintype "passive"))
      (node (ref "SW1") (pin "A") (pinfunction "P_A") (pintype "passive"))
      (node (ref "SW1") (pin "A'") (pinfunction "P1_A'") (pintype "passive"))
      (node (ref "SW3") (pin "1") (pinfunction "1_1") (pintype "passive"))
      (node (ref "SW3") (pin "2") (pinfunction "2_2") (pintype "passive"))
    )
    (net (code "9") (name "I2C_SCL") (class "Default")
      (node (ref "IC4") (pin "29") (pinfunction "PB10/SPI2_SCK/I2S_SCK/I2C2_SCL/USART3_TX_29") (pintype "bidirectional"))
      (node (ref "IC5") (pin "24") (pinfunction "SCLK_24") (pintype "bidirectional"))
      (node (ref "R24") (pin "1") (pinfunction "1_1") (pintype "passive"))
    )
    (net (code "10") (name "I2C_SDA") (class "Default")
      (node (ref "IC4") (pin "30") (pinfunction "PB11/I2C2_SDA/USART3_RX_30") (pintype "bidirectional"))
      (node (ref "IC5") (pin "23") (pinfunction "SDIN_23") (pintype "bidirectional"))
      (node (ref "R25") (pin "1") (pinfunction "1_1") (pintype "passive"))
    )
    (net (code "11") (name "I2S_LRCK") (class "Default")
      (node (ref "IC4") (pin "33") (pinfunction "PB12/SPI2_NSS/I2S2_WS/I2C2_SMBA/USART3_CK/TIM1_BKIN_33") (pintype "bidirectional"))
      (node (ref "IC5") (pin "5") (pinfunction "DACLRC_5") (pintype "bidirectional"))
      (node (ref "IC5") (pin "7") (pinfunction "ADCLRC_7") (pintype "bidirectional"))
    )
    (net (code "12") (name "I2S_SCK") (class "Default")
      (node (ref "IC4") (pin "34") (pinfunction "PB13/SPI2_SCK/I2S2_SCK/USART3_CTS/TIM1_CH1N_34") (pintype "bidirectional"))
      (node (ref "IC5") (pin "3") (pinfunction "BCLK_3") (pintype "bidirectional"))
    )
    (net (code "13") (name "I2S_SIN") (class "Default")
      (node (ref "IC4") (pin "35") (pinfunction "PB14/SPI2_MISO/USART3_RTS/TIM1_CH2N_35") (pintype "bidirectional"))
      (node (ref "IC5") (pin "6") (pinfunction "ADCDAT_6") (pintype "bidirectional"))
    )
    (net (code "14") (name "I2S_SOUT") (class "Default")
      (node (ref "IC4") (pin "36") (pinfunction "PB15/SPI2_MOSI/I2S2_SD/TIM1_CH3N_36") (pintype "bidirectional"))
      (node (ref "IC5") (pin "4") (pinfunction "DACDAT_4") (pintype "bidirectional"))
    )
    (net (code "15") (name "IN_1") (class "Default")
      (node (ref "C37") (pin "+") (pinfunction "+_+") (pintype "passive"))
      (node (ref "IC5") (pin "20") (pinfunction "LLINEIN_20") (pintype "bidirectional"))
    )
    (net (code "16") (name "IN_2") (class "Default")
      (node (ref "C43") (pin "+") (pinfunction "+_+") (pintype "passive"))
      (node (ref "IC5") (pin "19") (pinfunction "RLINEIN_19") (pintype "bidirectional"))
    )
    (net (code "17") (name "JTCK") (class "Default")
      (node (ref "IC4") (pin "49") (pinfunction "PA14/JTCK-SWCLK_49") (pintype "bidirectional"))
      (node (ref "JP1") (pin "4") (pinfunction "4_4") (pintype "passive"))
    )
    (net (code "18") (name "JTDI") (class "Default")
      (node (ref "IC4") (pin "50") (pinfunction "PA15/JTDI/SPI3_NSS/I2S3_WS_50") (pintype "bidirectional"))
      (node (ref "JP1") (pin "8") (pinfunction "8_8") (pintype "passive"))
    )
    (net (code "19") (name "JTDO") (class "Default")
      (node (ref "IC4") (pin "55") (pinfunction "PB3/JTDO/SPI3_SCK/I2S3_SCK_55") (pintype "bidirectional"))
      (node (ref "JP1") (pin "6") (pinfunction "6_6") (pintype "passive"))
    )
    (net (code "20") (name "JTMS") (class "Default")
      (node (ref "IC4") (pin "46") (pinfunction "PA13/JTMS-SWDAT_46") (pintype "bidirectional"))
      (node (ref "JP1") (pin "2") (pinfunction "2_2") (pintype "passive"))
    )
    (net (code "21") (name "LED_B") (class "Default")
      (node (ref "IC4") (pin "59") (pinfunction "PB7/I2C1_SDA/TIM4_CH2/USART1_RX_59") (pintype "bidirectional"))
      (node (ref "R4") (pin "1") (pinfunction "1_1") (pintype "passive"))
    )
    (net (code "22") (name "LED_CARRIER_G") (class "Default")
      (node (ref "IC4") (pin "25") (pinfunction "PC5/ADC15_25") (pintype "bidirectional"))
      (node (ref "R22") (pin "1") (pinfunction "1_1") (pintype "passive"))
    )
    (net (code "23") (name "LED_CARRIER_R") (class "Default")
      (node (ref "IC4") (pin "24") (pinfunction "PC4/ADC14_24") (pintype "bidirectional"))
      (node (ref "R21") (pin "1") (pinfunction "1_1") (pintype "passive"))
    )
    (net (code "24") (name "LED_G") (class "Default")
      (node (ref "IC4") (pin "58") (pinfunction "PB6/I2C1_SCL/TIM4_CH1/USART1_TX_58") (pintype "bidirectional"))
      (node (ref "R5") (pin "1") (pinfunction "1_1") (pintype "passive"))
    )
    (net (code "25") (name "LED_R") (class "Default")
      (node (ref "IC4") (pin "61") (pinfunction "PB8/TIM4_CH3/I2C1_SCL_61") (pintype "bidirectional"))
      (node (ref "R3") (pin "1") (pinfunction "1_1") (pintype "passive"))
    )
    (net (code "26") (name "LEVEL_1_CV") (class "Default")
      (node (ref "C8") (pin "2") (pinfunction "2_2") (pintype "passive"))
      (node (ref "IC3") (pin "8") (pinfunction "OUT_8") (pintype "output"))
      (node (ref "IC4") (pin "15") (pinfunction "PA1/USART2_RTS/UART4_RX/ADC1/TIM2_CH2_15") (pintype "bidirectional"))
      (node (ref "R13") (pin "1") (pinfunction "1_1") (pintype "passive"))
    )
    (net (code "27") (name "LEVEL_1_POT") (class "Default")
      (node (ref "C33") (pin "1") (pinfunction "1_1") (pintype "passive"))
      (node (ref "IC4") (pin "21") (pinfunction "PA5/SPI1_SCK/ADC5/DAC2_21") (pintype "bidirectional"))
      (node (ref "R26") (pin "P$2") (pinfunction "S_P$2") (pintype "passive"))
    )
    (net (code "28") (name "LEVEL_2_CV") (class "Default")
      (node (ref "C7") (pin "2") (pinfunction "2_2") (pintype "passive"))
      (node (ref "IC3") (pin "14") (pinfunction "OUT_14") (pintype "output"))
      (node (ref "IC4") (pin "16") (pinfunction "PA2/USART2_TX/ADC2/TIM2_CH3_16") (pintype "bidirectional"))
      (node (ref "R12") (pin "1") (pinfunction "1_1") (pintype "passive"))
    )
    (net (code "29") (name "LEVEL_2_POT") (class "Default")
      (node (ref "C31") (pin "1") (pinfunction "1_1") (pintype "passive"))
      (node (ref "IC4") (pin "22") (pinfunction "PA6/SPI1_MISO/ADC6/TIM3_CH1_22") (pintype "bidirectional"))
      (node (ref "R27") (pin "P$2") (pinfunction "S_P$2") (pintype "passive"))
    )
    (net (code "30") (name "MOD_OUT") (class "Default")
      (node (ref "C32") (pin "+") (pinfunction "+_+") (pintype "passive"))
      (node (ref "IC5") (pin "12") (pinfunction "LOUT_12") (pintype "bidirectional"))
    )
    (net (code "31") (name "NORMALIZATION_PROBE") (class "Default")
      (node (ref "D3") (pin "3") (pinfunction "AC_3") (pintype "passive"))
      (node (ref "IC4") (pin "39") (pinfunction "PC8_39") (pintype "bidirectional"))
      (node (ref "R32") (pin "1") (pinfunction "1_1") (pintype "passive"))
      (node (ref "R35") (pin "1") (pinfunction "1_1") (pintype "passive"))
      (node (ref "R40") (pin "2") (pinfunction "2_2") (pintype "passive"))
      (node (ref "R41") (pin "2") (pinfunction "2_2") (pintype "passive"))
    )
    (net (code "32") (name "Net-(C32-Pad-)") (class "Default")
      (node (ref "C32") (pin "-") (pinfunction "-_-") (pintype "passive"))
      (node (ref "R28") (pin "2") (pinfunction "2_2") (pintype "passive"))
      (node (ref "R29") (pin "2") (pinfunction "2_2") (pintype "passive"))
    )
    (net (code "33") (name "Net-(C37-Pad-)") (class "Default")
      (node (ref "C37") (pin "-") (pinfunction "-_-") (pintype "passive"))
      (node (ref "C44") (pin "1") (pinfunction "1_1") (pintype "passive"))
      (node (ref "R36") (pin "2") (pinfunction "2_2") (pintype "passive"))
      (node (ref "R37") (pin "1") (pinfunction "1_1") (pintype "passive"))
    )
    (net (code "34") (name "Net-(C39-Pad-)") (class "Default")
      (node (ref "C39") (pin "-") (pinfunction "-_-") (pintype "passive"))
      (node (ref "R33") (pin "2") (pinfunction "2_2") (pintype "passive"))
      (node (ref "R34") (pin "2") (pinfunction "2_2") (pintype "passive"))
    )
    (net (code "35") (name "Net-(C43-Pad-)") (class "Default")
      (node (ref "C43") (pin "-") (pinfunction "-_-") (pintype "passive"))
      (node (ref "C45") (pin "1") (pinfunction "1_1") (pintype "passive"))
      (node (ref "R38") (pin "1") (pinfunction "1_1") (pintype "passive"))
      (node (ref "R39") (pin "2") (pinfunction "2_2") (pintype "passive"))
    )
    (net (code "36") (name "Net-(D1-PadA)") (class "Default")
      (node (ref "D1") (pin "A") (pinfunction "A_A") (pintype "passive"))
      (node (ref "JP3") (pin "1") (pinfunction "1_1") (pintype "passive"))
      (node (ref "JP3") (pin "2") (pinfunction "2_2") (pintype "passive"))
    )
    (net (code "37") (name "Net-(D1-PadC)") (class "Default")
      (node (ref "D1") (pin "C") (pinfunction "C_C") (pintype "passive"))
      (node (ref "L1") (pin "2") (pinfunction "2_2") (pintype "passive"))
    )
    (net (code "38") (name "Net-(D2-PadA)") (class "Default")
      (node (ref "D2") (pin "A") (pinfunction "A_A") (pintype "passive"))
      (node (ref "L3") (pin "2") (pinfunction "2_2") (pintype "passive"))
    )
    (net (code "39") (name "Net-(D2-PadC)") (class "Default")
      (node (ref "D2") (pin "C") (pinfunction "C_C") (pintype "passive"))
      (node (ref "JP3") (pin "10") (pinfunction "10_10") (pintype "passive"))
      (node (ref "JP3") (pin "9") (pinfunction "9_9") (pintype "passive"))
    )
    (net (code "40") (name "Net-(IC1-VIN)") (class "Default")
      (node (ref "C2") (pin "+") (pinfunction "+_+") (pintype "passive"))
      (node (ref "IC1") (pin "2") (pinfunction "VIN_2") (pintype "input"))
      (node (ref "R1") (pin "1") (pinfunction "1_1") (pintype "passive"))
    )
    (net (code "41") (name "Net-(IC3A--IN)") (class "Default")
      (node (ref "C12") (pin "1") (pinfunction "1_1") (pintype "passive"))
      (node (ref "IC3") (pin "2") (pinfunction "-IN_2") (pintype "input"))
      (node (ref "R15") (pin "2") (pinfunction "2_2") (pintype "passive"))
      (node (ref "R17") (pin "1") (pinfunction "1_1") (pintype "passive"))
      (node (ref "R19") (pin "1") (pinfunction "1_1") (pintype "passive"))
    )
    (net (code "42") (name "Net-(IC3B--IN)") (class "Default")
      (node (ref "C14") (pin "1") (pinfunction "1_1") (pintype "passive"))
      (node (ref "IC3") (pin "6") (pinfunction "-IN_6") (pintype "input"))
      (node (ref "R16") (pin "2") (pinfunction "2_2") (pintype "passive"))
      (node (ref "R18") (pin "1") (pinfunction "1_1") (pintype "passive"))
      (node (ref "R20") (pin "1") (pinfunction "1_1") (pintype "passive"))
    )
    (net (code "43") (name "Net-(IC3C--IN)") (class "Default")
      (node (ref "C8") (pin "1") (pinfunction "1_1") (pintype "passive"))
      (node (ref "IC3") (pin "9") (pinfunction "-IN_9") (pintype "input"))
      (node (ref "R11") (pin "1") (pinfunction "1_1") (pintype "passive"))
      (node (ref "R13") (pin "2") (pinfunction "2_2") (pintype "passive"))
      (node (ref "R9") (pin "1") (pinfunction "1_1") (pintype "passive"))
    )
    (net (code "44") (name "Net-(IC3D--IN)") (class "Default")
      (node (ref "C7") (pin "1") (pinfunction "1_1") (pintype "passive"))
      (node (ref "IC3") (pin "13") (pinfunction "-IN_13") (pintype "input"))
      (node (ref "R10") (pin "1") (pinfunction "1_1") (pintype "passive"))
      (node (ref "R12") (pin "2") (pinfunction "2_2") (pintype "passive"))
      (node (ref "R8") (pin "1") (pinfunction "1_1") (pintype "passive"))
    )
    (net (code "45") (name "Net-(IC4-PB4{slash}NJTRST{slash}SPI3_MISO{slash}SPI1_MISO)") (class "Default")
      (node (ref "IC4") (pin "56") (pinfunction "PB4/NJTRST/SPI3_MISO/SPI1_MISO_56") (pintype "bidirectional"))
      (node (ref "TP3") (pin "P$1") (pinfunction "1_P$1") (pintype "bidirectional"))
    )
    (net (code "46") (name "Net-(IC4-PB5{slash}I2C1_SMBA{slash}SPI1_MOSI{slash}SPI3_MOSI{slash}I2S3_SD)") (class "Default")
      (node (ref "IC4") (pin "57") (pinfunction "PB5/I2C1_SMBA/SPI1_MOSI/SPI3_MOSI/I2S3_SD_57") (pintype "bidirectional"))
      (node (ref "TP2") (pin "P$1") (pinfunction "1_P$1") (pintype "bidirectional"))
    )
    (net (code "47") (name "Net-(IC4-PB9{slash}SPI2_NSS{slash}I2S2_WS{slash}I2C1_SDA{slash}TIM4_CH4)") (class "Default")
      (node (ref "IC4") (pin "62") (pinfunction "PB9/SPI2_NSS/I2S2_WS/I2C1_SDA/TIM4_CH4_62") (pintype "bidirectional"))
      (node (ref "TP1") (pin "P$1") (pinfunction "1_P$1") (pintype "bidirectional"))
    )
    (net (code "48") (name "Net-(IC4-PC11{slash}UART4_RX{slash}SPI3_MISO{slash}USART3_RX)") (class "Default")
      (node (ref "IC4") (pin "52") (pinfunction "PC11/UART4_RX/SPI3_MISO/USART3_RX_52") (pintype "bidirectional"))
      (node (ref "TP4") (pin "P$1") (pinfunction "1_P$1") (pintype "bidirectional"))
    )
    (net (code "49") (name "Net-(IC4-PD0{slash}OSC_IN)") (class "Default")
      (node (ref "C11") (pin "2") (pinfunction "2_2") (pintype "passive"))
      (node (ref "IC4") (pin "5") (pinfunction "PD0/OSC_IN_5") (pintype "bidirectional"))
      (node (ref "Q1") (pin "2") (pinfunction "2_2") (pintype "passive"))
    )
    (net (code "50") (name "Net-(IC4-PD1{slash}OSC_OUT)") (class "Default")
      (node (ref "C10") (pin "2") (pinfunction "2_2") (pintype "passive"))
      (node (ref "IC4") (pin "6") (pinfunction "PD1/OSC_OUT_6") (pintype "bidirectional"))
      (node (ref "Q1") (pin "1") (pinfunction "1_1") (pintype "passive"))
    )
    (net (code "51") (name "Net-(IC4-VCAP_1)") (class "Default")
      (node (ref "C19") (pin "1") (pinfunction "1_1") (pintype "passive"))
      (node (ref "IC4") (pin "31") (pinfunction "VCAP_1_31") (pintype "power_in"))
    )
    (net (code "52") (name "Net-(IC4-VCAP_2)") (class "Default")
      (node (ref "C22") (pin "1") (pinfunction "1_1") (pintype "passive"))
      (node (ref "IC4") (pin "47") (pinfunction "VCAP_2_47") (pintype "power_in"))
    )
    (net (code "53") (name "Net-(IC5-VMID)") (class "Default")
      (node (ref "C36") (pin "+") (pinfunction "+_+") (pintype "passive"))
      (node (ref "C42") (pin "1") (pinfunction "1_1") (pintype "passive"))
      (node (ref "IC5") (pin "16") (pinfunction "VMID_16") (pintype "bidirectional"))
    )
    (net (code "54") (name "Net-(IC5-XTI{slash}MCLK)") (class "Default")
      (node (ref "C41") (pin "2") (pinfunction "2_2") (pintype "passive"))
      (node (ref "IC5") (pin "25") (pinfunction "XTI/MCLK_25") (pintype "bidirectional"))
      (node (ref "Q2") (pin "2") (pinfunction "2_2") (pintype "passive"))
    )
    (net (code "55") (name "Net-(IC5-XTO)") (class "Default")
      (node (ref "C26") (pin "2") (pinfunction "2_2") (pintype "passive"))
      (node (ref "IC5") (pin "26") (pinfunction "XTO_26") (pintype "bidirectional"))
      (node (ref "Q2") (pin "1") (pinfunction "1_1") (pintype "passive"))
    )
    (net (code "56") (name "Net-(IC6A--IN)") (class "Default")
      (node (ref "C35") (pin "1") (pinfunction "1_1") (pintype "passive"))
      (node (ref "IC6") (pin "2") (pinfunction "-IN_2") (pintype "input"))
      (node (ref "R29") (pin "1") (pinfunction "1_1") (pintype "passive"))
      (node (ref "R30") (pin "2") (pinfunction "2_2") (pintype "passive"))
    )
    (net (code "57") (name "Net-(IC6A-OUT)") (class "Default")
      (node (ref "C35") (pin "2") (pinfunction "2_2") (pintype "passive"))
      (node (ref "IC6") (pin "1") (pinfunction "OUT_1") (pintype "output"))
      (node (ref "R30") (pin "1") (pinfunction "1_1") (pintype "passive"))
      (node (ref "R42") (pin "2") (pinfunction "2_2") (pintype "passive"))
    )
    (net (code "58") (name "Net-(IC6B--IN)") (class "Default")
      (node (ref "C38") (pin "1") (pinfunction "1_1") (pintype "passive"))
      (node (ref "IC6") (pin "6") (pinfunction "-IN_6") (pintype "input"))
      (node (ref "R31") (pin "2") (pinfunction "2_2") (pintype "passive"))
      (node (ref "R34") (pin "1") (pinfunction "1_1") (pintype "passive"))
    )
    (net (code "59") (name "Net-(IC6B-OUT)") (class "Default")
      (node (ref "C38") (pin "2") (pinfunction "2_2") (pintype "passive"))
      (node (ref "IC6") (pin "7") (pinfunction "OUT_7") (pintype "output"))
      (node (ref "R31") (pin "1") (pinfunction "1_1") (pintype "passive"))
      (node (ref "R43") (pin "2") (pinfunction "2_2") (pintype "passive"))
    )
    (net (code "60") (name "Net-(J1-2)") (class "Default")
      (node (ref "J1") (pin "P2") (pinfunction "2_P2") (pintype "passive"))
      (node (ref "R32") (pin "2") (pinfunction "2_2") (pintype "passive"))
    )
    (net (code "61") (name "Net-(J1-3)") (class "Default")
      (node (ref "J1") (pin "P3") (pinfunction "3_P3") (pintype "passive"))
      (node (ref "R9") (pin "2") (pinfunction "2_2") (pintype "passive"))
    )
    (net (code "62") (name "Net-(J2-2)") (class "Default")
      (node (ref "J2") (pin "P2") (pinfunction "2_P2") (pintype "passive"))
      (node (ref "R35") (pin "2") (pinfunction "2_2") (pintype "passive"))
    )
    (net (code "63") (name "Net-(J2-3)") (class "Default")
      (node (ref "J2") (pin "P3") (pinfunction "3_P3") (pintype "passive"))
      (node (ref "R8") (pin "2") (pinfunction "2_2") (pintype "passive"))
    )
    (net (code "64") (name "Net-(J3-3)") (class "Default")
      (node (ref "J3") (pin "P3") (pinfunction "3_P3") (pintype "passive"))
      (node (ref "R17") (pin "2") (pinfunction "2_2") (pintype "passive"))
    )
    (net (code "65") (name "Net-(J4-3)") (class "Default")
      (node (ref "J4") (pin "P3") (pinfunction "3_P3") (pintype "passive"))
      (node (ref "R18") (pin "2") (pinfunction "2_2") (pintype "passive"))
    )
    (net (code "66") (name "Net-(J5-2)") (class "Default")
      (node (ref "J5") (pin "P2") (pinfunction "2_P2") (pintype "passive"))
      (node (ref "R40") (pin "1") (pinfunction "1_1") (pintype "passive"))
    )
    (net (code "67") (name "Net-(J5-3)") (class "Default")
      (node (ref "J5") (pin "P3") (pinfunction "3_P3") (pintype "passive"))
      (node (ref "R37") (pin "2") (pinfunction "2_2") (pintype "passive"))
    )
    (net (code "68") (name "Net-(J6-2)") (class "Default")
      (node (ref "J6") (pin "P2") (pinfunction "2_P2") (pintype "passive"))
      (node (ref "R41") (pin "1") (pinfunction "1_1") (pintype "passive"))
    )
    (net (code "69") (name "Net-(J6-3)") (class "Default")
      (node (ref "J6") (pin "P3") (pinfunction "3_P3") (pintype "passive"))
      (node (ref "R38") (pin "2") (pinfunction "2_2") (pintype "passive"))
    )
    (net (code "70") (name "Net-(J7-3)") (class "Default")
      (node (ref "J7") (pin "P3") (pinfunction "3_P3") (pintype "passive"))
      (node (ref "R42") (pin "1") (pinfunction "1_1") (pintype "passive"))
    )
    (net (code "71") (name "Net-(J8-3)") (class "Default")
      (node (ref "J8") (pin "P3") (pinfunction "3_P3") (pintype "passive"))
      (node (ref "R43") (pin "1") (pinfunction "1_1") (pintype "passive"))
    )
    (net (code "72") (name "Net-(LED1-PadBLU)") (class "Default")
      (node (ref "LED1") (pin "BLU") (pinfunction "BLU_BLU") (pintype "bidirectional"))
      (node (ref "R4") (pin "2") (pinfunction "2_2") (pintype "passive"))
    )
    (net (code "73") (name "Net-(LED1-PadGRN)") (class "Default")
      (node (ref "LED1") (pin "GRN") (pinfunction "GRN_GRN") (pintype "bidirectional"))
      (node (ref "R5") (pin "2") (pinfunction "2_2") (pintype "passive"))
    )
    (net (code "74") (name "Net-(LED1-PadRED)") (class "Default")
      (node (ref "LED1") (pin "RED") (pinfunction "RED_RED") (pintype "bidirectional"))
      (node (ref "R3") (pin "2") (pinfunction "2_2") (pintype "passive"))
    )
    (net (code "75") (name "Net-(LED2-GRN)") (class "Default")
      (node (ref "LED2") (pin "1") (pinfunction "GRN_1") (pintype "bidirectional"))
      (node (ref "R22") (pin "2") (pinfunction "2_2") (pintype "passive"))
    )
    (net (code "76") (name "Net-(LED2-RED)") (class "Default")
      (node (ref "LED2") (pin "3") (pinfunction "RED_3") (pintype "bidirectional"))
      (node (ref "R21") (pin "2") (pinfunction "2_2") (pintype "passive"))
    )
    (net (code "77") (name "PARAMETER_CV") (class "Default")
      (node (ref "C14") (pin "2") (pinfunction "2_2") (pintype "passive"))
      (node (ref "IC3") (pin "7") (pinfunction "OUT_7") (pintype "output"))
      (node (ref "IC4") (pin "17") (pinfunction "PA3/USART2_RX/ADC3/TIM2_CH4_17") (pintype "bidirectional"))
      (node (ref "R16") (pin "1") (pinfunction "1_1") (pintype "passive"))
    )
    (net (code "78") (name "PARAMETER_POT") (class "Default")
      (node (ref "C25") (pin "1") (pinfunction "1_1") (pintype "passive"))
      (node (ref "IC4") (pin "23") (pinfunction "PA7/SPI1_MOSI/ADC7/TIM3_CH2_23") (pintype "bidirectional"))
      (node (ref "R23") (pin "P$2") (pinfunction "S_P$2") (pintype "passive"))
    )
    (net (code "79") (name "RESET") (class "Default")
      (node (ref "IC4") (pin "7") (pinfunction "NRST_7") (pintype "bidirectional"))
      (node (ref "JP1") (pin "10") (pinfunction "10_10") (pintype "passive"))
      (node (ref "R2") (pin "1") (pinfunction "1_1") (pintype "passive"))
      (node (ref "SW1") (pin "B") (pinfunction "S_B") (pintype "passive"))
      (node (ref "SW1") (pin "B'") (pinfunction "S1_B'") (pintype "passive"))
    )
    (net (code "80") (name "RX") (class "Default")
      (node (ref "IC4") (pin "43") (pinfunction "PA10/USART1_RX/TIM1_CH3_43") (pintype "bidirectional"))
      (node (ref "JP2") (pin "4") (pinfunction "4_4") (pintype "passive"))
    )
    (net (code "81") (name "SW_CARRIER") (class "Default")
      (node (ref "IC4") (pin "27") (pinfunction "PB1/ADC9/TIM3_CH4_27") (pintype "bidirectional"))
      (node (ref "SW3") (pin "3") (pinfunction "3_3") (pintype "passive"))
      (node (ref "SW3") (pin "4") (pinfunction "4_4") (pintype "passive"))
    )
    (net (code "82") (name "TX") (class "Default")
      (node (ref "IC4") (pin "42") (pinfunction "PA9/USART1_TX/TIM1_CH2_42") (pintype "bidirectional"))
      (node (ref "JP2") (pin "5") (pinfunction "5_5") (pintype "passive"))
    )
    (net (code "83") (name "VBAT") (class "Default")
      (node (ref "IC4") (pin "1") (pinfunction "VBAT_1") (pintype "power_in"))
    )
    (net (code "84") (name "VCC") (class "Default")
      (node (ref "C1") (pin "+") (pinfunction "+_+") (pintype "passive"))
      (node (ref "C34") (pin "1") (pinfunction "1_1") (pintype "passive"))
      (node (ref "IC6") (pin "8") (pinfunction "V+_8") (pintype "power_in"))
      (node (ref "L1") (pin "1") (pinfunction "1_1") (pintype "passive"))
      (node (ref "R1") (pin "2") (pinfunction "2_2") (pintype "passive"))
    )
    (net (code "85") (name "VEE") (class "Default")
      (node (ref "C3") (pin "-") (pinfunction "-_-") (pintype "passive"))
      (node (ref "C40") (pin "2") (pinfunction "2_2") (pintype "passive"))
      (node (ref "IC6") (pin "4") (pinfunction "V-_4") (pintype "power_in"))
      (node (ref "L3") (pin "1") (pinfunction "1_1") (pintype "passive"))
      (node (ref "R6") (pin "1") (pinfunction "1_1") (pintype "passive"))
    )
    (net (code "86") (name "unconnected-(IC4-PA8{slash}USART1_CK{slash}TIM1_CH1{slash}MCO-Pad41)") (class "Default")
      (node (ref "IC4") (pin "41") (pinfunction "PA8/USART1_CK/TIM1_CH1/MCO_41") (pintype "bidirectional"))
    )
    (net (code "87") (name "unconnected-(IC4-PA11{slash}USART1_CTS{slash}CANRX{slash}USBDM{slash}TIM1_CH4-Pad44)") (class "Default")
      (node (ref "IC4") (pin "44") (pinfunction "PA11/USART1_CTS/CANRX/USBDM/TIM1_CH4_44") (pintype "bidirectional"))
    )
    (net (code "88") (name "unconnected-(IC4-PA12{slash}USART1_RTS{slash}CANTX{slash}USBDP{slash}TIM1_ETR-Pad45)") (class "Default")
      (node (ref "IC4") (pin "45") (pinfunction "PA12/USART1_RTS/CANTX/USBDP/TIM1_ETR_45") (pintype "bidirectional"))
    )
    (net (code "89") (name "unconnected-(IC4-PC0{slash}ADC10-Pad8)") (class "Default")
      (node (ref "IC4") (pin "8") (pinfunction "PC0/ADC10_8") (pintype "bidirectional"))
    )
    (net (code "90") (name "unconnected-(IC4-PC1{slash}ADC11-Pad9)") (class "Default")
      (node (ref "IC4") (pin "9") (pinfunction "PC1/ADC11_9") (pintype "bidirectional"))
    )
    (net (code "91") (name "unconnected-(IC4-PC2{slash}SPI2_MISO{slash}ADC12-Pad10)") (class "Default")
      (node (ref "IC4") (pin "10") (pinfunction "PC2/SPI2_MISO/ADC12_10") (pintype "bidirectional"))
    )
    (net (code "92") (name "unconnected-(IC4-PC3{slash}SPI2_MOSI{slash}I2S2_SD{slash}ADC13-Pad11)") (class "Default")
      (node (ref "IC4") (pin "11") (pinfunction "PC3/SPI2_MOSI/I2S2_SD/ADC13_11") (pintype "bidirectional"))
    )
    (net (code "93") (name "unconnected-(IC4-PC6{slash}I2S2_MCK-Pad37)") (class "Default")
      (node (ref "IC4") (pin "37") (pinfunction "PC6/I2S2_MCK_37") (pintype "bidirectional"))
    )
    (net (code "94") (name "unconnected-(IC4-PC7{slash}I2S3_MCK-Pad38)") (class "Default")
      (node (ref "IC4") (pin "38") (pinfunction "PC7/I2S3_MCK_38") (pintype "bidirectional"))
    )
    (net (code "95") (name "unconnected-(IC4-PC9{slash}I2S2_CKIN{slash}I2S3_CKIN-Pad40)") (class "Default")
      (node (ref "IC4") (pin "40") (pinfunction "PC9/I2S2_CKIN/I2S3_CKIN_40") (pintype "bidirectional"))
    )
    (net (code "96") (name "unconnected-(IC4-PC10{slash}SPI3_SCK{slash}I2S3_SCK{slash}UART4_TX-Pad51)") (class "Default")
      (node (ref "IC4") (pin "51") (pinfunction "PC10/SPI3_SCK/I2S3_SCK/UART4_TX_51") (pintype "bidirectional"))
    )
    (net (code "97") (name "unconnected-(IC4-PC12{slash}UART5_TX{slash}I2S3_SD{slash}USART3_CK-Pad53)") (class "Default")
      (node (ref "IC4") (pin "53") (pinfunction "PC12/UART5_TX/I2S3_SD/USART3_CK_53") (pintype "bidirectional"))
    )
    (net (code "98") (name "unconnected-(IC4-PC13-TAMPER-RTC-Pad2)") (class "Default")
      (node (ref "IC4") (pin "2") (pinfunction "PC13-TAMPER-RTC_2") (pintype "bidirectional"))
    )
    (net (code "99") (name "unconnected-(IC4-PC14{slash}OSC32_IN-Pad3)") (class "Default")
      (node (ref "IC4") (pin "3") (pinfunction "PC14/OSC32_IN_3") (pintype "bidirectional"))
    )
    (net (code "100") (name "unconnected-(IC4-PC15{slash}OSC_OUT-Pad4)") (class "Default")
      (node (ref "IC4") (pin "4") (pinfunction "PC15/OSC_OUT_4") (pintype "bidirectional"))
    )
    (net (code "101") (name "unconnected-(IC4-PD2{slash}TIM3-ETR-Pad54)") (class "Default")
      (node (ref "IC4") (pin "54") (pinfunction "PD2/TIM3-ETR_54") (pintype "bidirectional"))
    )
    (net (code "102") (name "unconnected-(IC5-CLKOUT-Pad2)") (class "Default")
      (node (ref "IC5") (pin "2") (pinfunction "CLKOUT_2") (pintype "bidirectional"))
    )
    (net (code "103") (name "unconnected-(IC5-LHPOUT-Pad9)") (class "Default")
      (node (ref "IC5") (pin "9") (pinfunction "LHPOUT_9") (pintype "bidirectional"))
    )
    (net (code "104") (name "unconnected-(IC5-MICBIAS-Pad17)") (class "Default")
      (node (ref "IC5") (pin "17") (pinfunction "MICBIAS_17") (pintype "bidirectional"))
    )
    (net (code "105") (name "unconnected-(IC5-MICIN-Pad18)") (class "Default")
      (node (ref "IC5") (pin "18") (pinfunction "MICIN_18") (pintype "bidirectional"))
    )
    (net (code "106") (name "unconnected-(IC5-RHPOUT-Pad10)") (class "Default")
      (node (ref "IC5") (pin "10") (pinfunction "RHPOUT_10") (pintype "bidirectional"))
    )
    (net (code "107") (name "unconnected-(J3-2-PadP2)") (class "Default")
      (node (ref "J3") (pin "P2") (pinfunction "2_P2") (pintype "passive"))
    )
    (net (code "108") (name "unconnected-(J4-2-PadP2)") (class "Default")
      (node (ref "J4") (pin "P2") (pinfunction "2_P2") (pintype "passive"))
    )
    (net (code "109") (name "unconnected-(J7-2-PadP2)") (class "Default")
      (node (ref "J7") (pin "P2") (pinfunction "2_P2") (pintype "passive"))
    )
    (net (code "110") (name "unconnected-(J8-2-PadP2)") (class "Default")
      (node (ref "J8") (pin "P2") (pinfunction "2_P2") (pintype "passive"))
    )
    (net (code "111") (name "unconnected-(JP1-Pad7)") (class "Default")
      (node (ref "JP1") (pin "7") (pinfunction "7_7") (pintype "passive"))
    )
    (net (code "112") (name "unconnected-(JP2-Pad2)") (class "Default")
      (node (ref "JP2") (pin "2") (pinfunction "2_2") (pintype "passive"))
    )
    (net (code "113") (name "unconnected-(JP2-Pad3)") (class "Default")
      (node (ref "JP2") (pin "3") (pinfunction "3_3") (pintype "passive"))
    )
    (net (code "114") (name "unconnected-(JP2-Pad6)") (class "Default")
      (node (ref "JP2") (pin "6") (pinfunction "6_6") (pintype "passive"))
    )
  )
)
